# CATS-Vega-Storage.net
KiCad netlist of a schematic drawn in Altium Designer
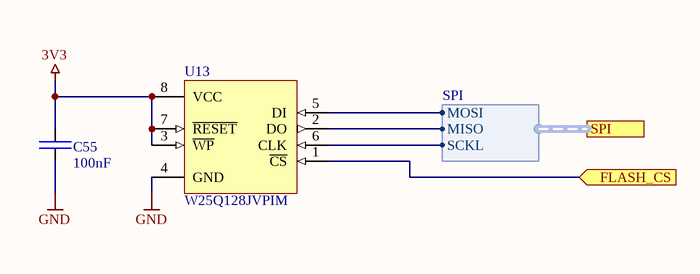
[diagram p0: CATS-Vega-Storage.SchDoc]

(export (version "E")
  (design (tool "Eeschema 10.0.6"))
  (components
    (comp (ref "C55")
      (value "100nF")
      (footprint "SMD Keramikkondensator 0603")
      (description "SMD Ceramic Capacitor E6")
      (libsource (lib "CATS-EUROC") (part "E6 - 100nF"))
    )
    (comp (ref "U13")
      (value "W25Q128JVPIM")
      (footprint "SMD IC WSON-8 (6x5)")
      (description "3V 128M-BIT\r\nSERIAL FLASH MEMORY WITH\r\nDUAL/QUAD SPI & QPI & DTR")
      (libsource (lib "Digital") (part "W25Q128JVPIM"))
    )
  )
  (nets
    (net (code "2") (name "/FLASH_CS") (class "Default")
      (node (ref "U13") (pin "1") (pinfunction "~{CS}_1") (pintype "input"))
    )
    (net (code "3") (name "/MISO") (class "Default")
      (node (ref "U13") (pin "2") (pinfunction "DO_2") (pintype "output"))
    )
    (net (code "4") (name "/MOSI") (class "Default")
      (node (ref "U13") (pin "5") (pinfunction "DI_5") (pintype "input"))
    )
    (net (code "5") (name "/SCKL") (class "Default")
      (node (ref "U13") (pin "6") (pinfunction "CLK_6") (pintype "input"))
    )
    (net (code "7") (name "3V3") (class "Default")
      (node (ref "C55") (pin "2") (pinfunction "2_2") (pintype "passive"))
      (node (ref "U13") (pin "3") (pinfunction "~{WP}_3") (pintype "input"))
      (node (ref "U13") (pin "7") (pinfunction "~{RESET}_7") (pintype "input"))
      (node (ref "U13") (pin "8") (pinfunction "VCC_8") (pintype "power_in"))
    )
    (net (code "8") (name "GND") (class "Default")
      (node (ref "C55") (pin "1") (pinfunction "1_1") (pintype "passive"))
      (node (ref "U13") (pin "4") (pinfunction "GND_4") (pintype "power_in"))
    )
  )
)
